# MiniDC.net
KiCad netlist of a schematic drawn in EAGLE
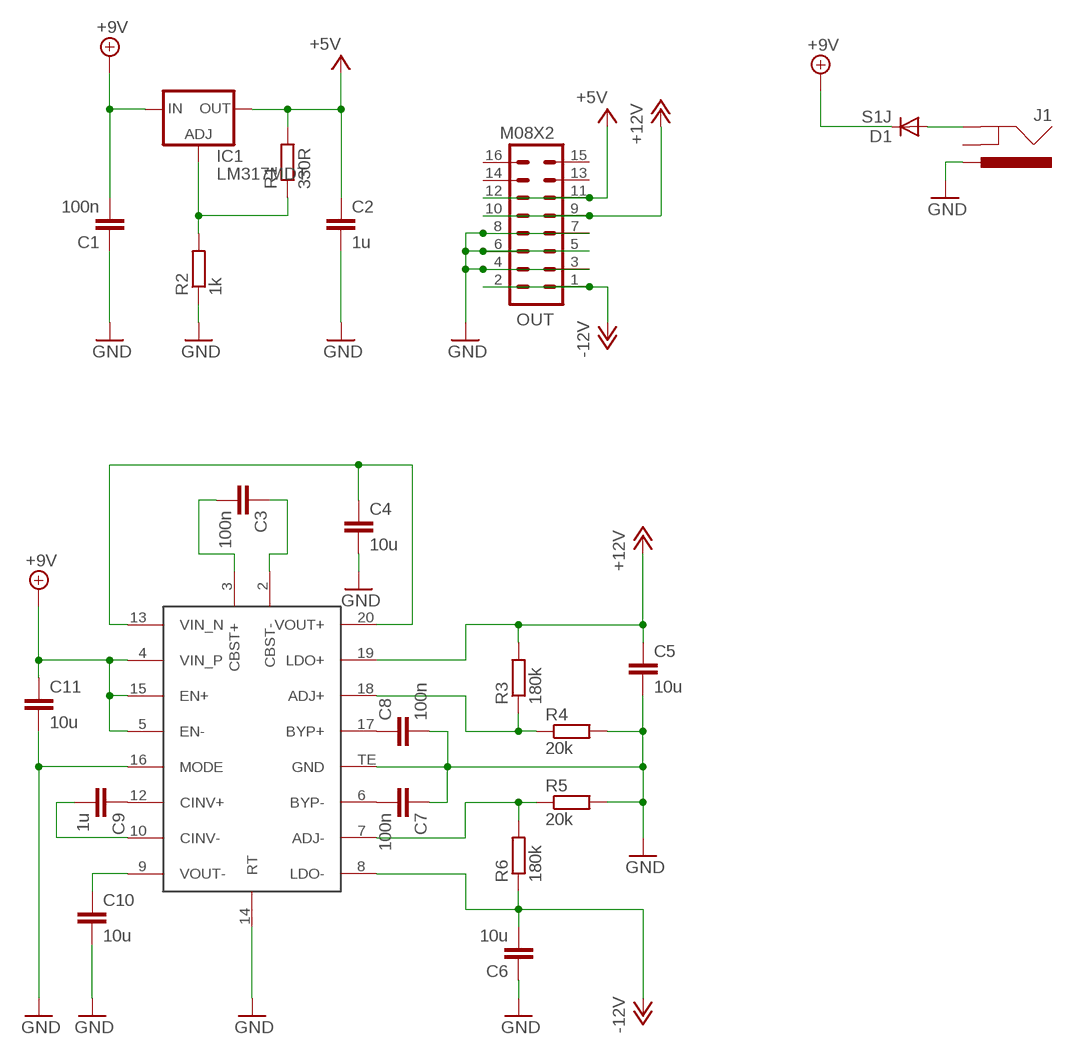
[diagram p0: schematic, sheet 1]

(export (version "E")
  (design (tool "Eeschema 10.0.6"))
  (components
    (comp (ref "C1")
      (value "100n")
      (footprint "eagle-import:C0603")
      (libsource (lib "eagle-import") (part "rcl_C-EUC0603"))
    )
    (comp (ref "C2")
      (value "1u")
      (footprint "eagle-import:C1206K")
      (libsource (lib "eagle-import") (part "C-EUC1206K"))
    )
    (comp (ref "C3")
      (value "100n")
      (footprint "eagle-import:C0603")
      (libsource (lib "eagle-import") (part "rcl_C-EUC0603"))
    )
    (comp (ref "C4")
      (value "10u")
      (footprint "eagle-import:C1206K")
      (libsource (lib "eagle-import") (part "C-EUC1206K"))
    )
    (comp (ref "C5")
      (value "10u")
      (footprint "eagle-import:C1206K")
      (libsource (lib "eagle-import") (part "C-EUC1206K"))
    )
    (comp (ref "C6")
      (value "10u")
      (footprint "eagle-import:C1206K")
      (libsource (lib "eagle-import") (part "C-EUC1206K"))
    )
    (comp (ref "C7")
      (value "100n")
      (footprint "eagle-import:C0603")
      (libsource (lib "eagle-import") (part "rcl_C-EUC0603"))
    )
    (comp (ref "C8")
      (value "100n")
      (footprint "eagle-import:C0603")
      (libsource (lib "eagle-import") (part "rcl_C-EUC0603"))
    )
    (comp (ref "C9")
      (value "1u")
      (footprint "eagle-import:C1206")
      (libsource (lib "eagle-import") (part "C-EUC1206"))
    )
    (comp (ref "C10")
      (value "10u")
      (footprint "eagle-import:C1206K")
      (libsource (lib "eagle-import") (part "C-EUC1206K"))
    )
    (comp (ref "C11")
      (value "10u")
      (footprint "eagle-import:C1206K")
      (libsource (lib "eagle-import") (part "C-EUC1206K"))
    )
    (comp (ref "D1")
      (value "S1J")
      (footprint "eagle-import:SMA-DIODE")
      (libsource (lib "eagle-import") (part "DIODESMA"))
    )
    (comp (ref "IC1")
      (value "LM317MDT")
      (footprint "eagle-import:DPACK")
      (libsource (lib "eagle-import") (part "LM317?MDT"))
    )
    (comp (ref "IC2")
      (value "LTC3265")
      (footprint "eagle-import:TSSOP20-TE")
      (libsource (lib "eagle-import") (part "LTC3265"))
    )
    (comp (ref "J1")
      (value "POWER_JACKPTH")
      (footprint "eagle-import:POWER_JACK_PTH")
      (libsource (lib "eagle-import") (part "POWER_JACKPTH"))
    )
    (comp (ref "OUT")
      (value "M08X2")
      (footprint "eagle-import:2X8")
      (libsource (lib "eagle-import") (part "M08X2"))
    )
    (comp (ref "R1")
      (value "330R")
      (footprint "eagle-import:0603")
      (libsource (lib "eagle-import") (part "R-EU_0603"))
    )
    (comp (ref "R2")
      (value "1k")
      (footprint "eagle-import:0603")
      (libsource (lib "eagle-import") (part "R-EU_0603"))
    )
    (comp (ref "R3")
      (value "180k")
      (footprint "eagle-import:0603")
      (libsource (lib "eagle-import") (part "R-EU_0603"))
    )
    (comp (ref "R4")
      (value "20k")
      (footprint "eagle-import:0603")
      (libsource (lib "eagle-import") (part "R-EU_0603"))
    )
    (comp (ref "R5")
      (value "20k")
      (footprint "eagle-import:0603")
      (libsource (lib "eagle-import") (part "R-EU_0603"))
    )
    (comp (ref "R6")
      (value "180k")
      (footprint "eagle-import:0603")
      (libsource (lib "eagle-import") (part "R-EU_0603"))
    )
  )
  (nets
    (net (code "1") (name "+5V") (class "Default")
      (node (ref "C2") (pin "1") (pinfunction "1_1") (pintype "passive"))
      (node (ref "IC1") (pin "4") (pinfunction "OUT_4") (pintype "passive"))
      (node (ref "OUT") (pin "11") (pinfunction "11_11") (pintype "passive"))
      (node (ref "OUT") (pin "12") (pinfunction "12_12") (pintype "passive"))
      (node (ref "R1") (pin "2") (pinfunction "2_2") (pintype "passive"))
    )
    (net (code "2") (name "+9V") (class "Default")
      (node (ref "C1") (pin "2") (pinfunction "2_2") (pintype "passive"))
      (node (ref "C11") (pin "1") (pinfunction "1_1") (pintype "passive"))
      (node (ref "D1") (pin "C") (pinfunction "C_C") (pintype "passive"))
      (node (ref "IC1") (pin "3") (pinfunction "IN_3") (pintype "input"))
      (node (ref "IC2") (pin "15") (pinfunction "EN+_15") (pintype "bidirectional"))
      (node (ref "IC2") (pin "4") (pinfunction "VIN_P_4") (pintype "bidirectional"))
      (node (ref "IC2") (pin "5") (pinfunction "EN-_5") (pintype "bidirectional"))
    )
    (net (code "3") (name "+12V") (class "Default")
      (node (ref "C5") (pin "1") (pinfunction "1_1") (pintype "passive"))
      (node (ref "IC2") (pin "19") (pinfunction "LDO+_19") (pintype "bidirectional"))
      (node (ref "OUT") (pin "10") (pinfunction "10_10") (pintype "passive"))
      (node (ref "OUT") (pin "9") (pinfunction "9_9") (pintype "passive"))
      (node (ref "R3") (pin "2") (pinfunction "2_2") (pintype "passive"))
    )
    (net (code "4") (name "-12V") (class "Default")
      (node (ref "C6") (pin "2") (pinfunction "2_2") (pintype "passive"))
      (node (ref "IC2") (pin "8") (pinfunction "LDO-_8") (pintype "bidirectional"))
      (node (ref "OUT") (pin "1") (pinfunction "1_1") (pintype "passive"))
      (node (ref "OUT") (pin "2") (pinfunction "2_2") (pintype "passive"))
      (node (ref "R6") (pin "1") (pinfunction "1_1") (pintype "passive"))
    )
    (net (code "5") (name "GND") (class "Default")
      (node (ref "C1") (pin "1") (pinfunction "1_1") (pintype "passive"))
      (node (ref "C10") (pin "2") (pinfunction "2_2") (pintype "passive"))
      (node (ref "C11") (pin "2") (pinfunction "2_2") (pintype "passive"))
      (node (ref "C2") (pin "2") (pinfunction "2_2") (pintype "passive"))
      (node (ref "C4") (pin "2") (pinfunction "2_2") (pintype "passive"))
      (node (ref "C5") (pin "2") (pinfunction "2_2") (pintype "passive"))
      (node (ref "C6") (pin "1") (pinfunction "1_1") (pintype "passive"))
      (node (ref "C7") (pin "1") (pinfunction "1_1") (pintype "passive"))
      (node (ref "C8") (pin "2") (pinfunction "2_2") (pintype "passive"))
      (node (ref "IC2") (pin "14") (pinfunction "RT_14") (pintype "bidirectional"))
      (node (ref "IC2") (pin "16") (pinfunction "MODE_16") (pintype "bidirectional"))
      (node (ref "IC2") (pin "TE") (pinfunction "GND_TE") (pintype "bidirectional"))
      (node (ref "J1") (pin "PWR") (pinfunction "PWR_PWR") (pintype "bidirectional"))
      (node (ref "OUT") (pin "3") (pinfunction "3_3") (pintype "passive"))
      (node (ref "OUT") (pin "4") (pinfunction "4_4") (pintype "passive"))
      (node (ref "OUT") (pin "5") (pinfunction "5_5") (pintype "passive"))
      (node (ref "OUT") (pin "6") (pinfunction "6_6") (pintype "passive"))
      (node (ref "OUT") (pin "7") (pinfunction "7_7") (pintype "passive"))
      (node (ref "OUT") (pin "8") (pinfunction "8_8") (pintype "passive"))
      (node (ref "R2") (pin "1") (pinfunction "1_1") (pintype "passive"))
      (node (ref "R4") (pin "2") (pinfunction "2_2") (pintype "passive"))
      (node (ref "R5") (pin "2") (pinfunction "2_2") (pintype "passive"))
    )
    (net (code "6") (name "Net-(D1-PadA)") (class "Default")
      (node (ref "D1") (pin "A") (pinfunction "A_A") (pintype "passive"))
      (node (ref "J1") (pin "GND") (pinfunction "GND_GND") (pintype "bidirectional"))
    )
    (net (code "7") (name "Net-(IC1-ADJ)") (class "Default")
      (node (ref "IC1") (pin "1") (pinfunction "ADJ_1") (pintype "input"))
      (node (ref "R1") (pin "1") (pinfunction "1_1") (pintype "passive"))
      (node (ref "R2") (pin "2") (pinfunction "2_2") (pintype "passive"))
    )
    (net (code "8") (name "Net-(IC2-ADJ+)") (class "Default")
      (node (ref "IC2") (pin "18") (pinfunction "ADJ+_18") (pintype "bidirectional"))
      (node (ref "R3") (pin "1") (pinfunction "1_1") (pintype "passive"))
      (node (ref "R4") (pin "1") (pinfunction "1_1") (pintype "passive"))
    )
    (net (code "9") (name "Net-(IC2-ADJ-)") (class "Default")
      (node (ref "IC2") (pin "7") (pinfunction "ADJ-_7") (pintype "bidirectional"))
      (node (ref "R5") (pin "1") (pinfunction "1_1") (pintype "passive"))
      (node (ref "R6") (pin "2") (pinfunction "2_2") (pintype "passive"))
    )
    (net (code "10") (name "Net-(IC2-BYP+)") (class "Default")
      (node (ref "C8") (pin "1") (pinfunction "1_1") (pintype "passive"))
      (node (ref "IC2") (pin "17") (pinfunction "BYP+_17") (pintype "bidirectional"))
    )
    (net (code "11") (name "Net-(IC2-BYP-)") (class "Default")
      (node (ref "C7") (pin "2") (pinfunction "2_2") (pintype "passive"))
      (node (ref "IC2") (pin "6") (pinfunction "BYP-_6") (pintype "bidirectional"))
    )
    (net (code "12") (name "Net-(IC2-CBST+)") (class "Default")
      (node (ref "C3") (pin "2") (pinfunction "2_2") (pintype "passive"))
      (node (ref "IC2") (pin "3") (pinfunction "CBST+_3") (pintype "bidirectional"))
    )
    (net (code "13") (name "Net-(IC2-CBST-)") (class "Default")
      (node (ref "C3") (pin "1") (pinfunction "1_1") (pintype "passive"))
      (node (ref "IC2") (pin "2") (pinfunction "CBST-_2") (pintype "bidirectional"))
    )
    (net (code "14") (name "Net-(IC2-CINV+)") (class "Default")
      (node (ref "C9") (pin "1") (pinfunction "1_1") (pintype "passive"))
      (node (ref "IC2") (pin "12") (pinfunction "CINV+_12") (pintype "bidirectional"))
    )
    (net (code "15") (name "Net-(IC2-CINV-)") (class "Default")
      (node (ref "C9") (pin "2") (pinfunction "2_2") (pintype "passive"))
      (node (ref "IC2") (pin "10") (pinfunction "CINV-_10") (pintype "bidirectional"))
    )
    (net (code "16") (name "Net-(IC2-VIN_N)") (class "Default")
      (node (ref "C4") (pin "1") (pinfunction "1_1") (pintype "passive"))
      (node (ref "IC2") (pin "13") (pinfunction "VIN_N_13") (pintype "bidirectional"))
      (node (ref "IC2") (pin "20") (pinfunction "VOUT+_20") (pintype "bidirectional"))
    )
    (net (code "17") (name "Net-(IC2-VOUT-)") (class "Default")
      (node (ref "C10") (pin "1") (pinfunction "1_1") (pintype "passive"))
      (node (ref "IC2") (pin "9") (pinfunction "VOUT-_9") (pintype "bidirectional"))
    )
    (net (code "18") (name "unconnected-(J1-PadGNDBREAK)") (class "Default")
      (node (ref "J1") (pin "GNDBREAK") (pinfunction "GNDBREAK_GNDBREAK") (pintype "bidirectional"))
    )
    (net (code "19") (name "unconnected-(OUT-Pad13)") (class "Default")
      (node (ref "OUT") (pin "13") (pinfunction "13_13") (pintype "passive"))
    )
    (net (code "20") (name "unconnected-(OUT-Pad14)") (class "Default")
      (node (ref "OUT") (pin "14") (pinfunction "14_14") (pintype "passive"))
    )
    (net (code "21") (name "unconnected-(OUT-Pad15)") (class "Default")
      (node (ref "OUT") (pin "15") (pinfunction "15_15") (pintype "passive"))
    )
    (net (code "22") (name "unconnected-(OUT-Pad16)") (class "Default")
      (node (ref "OUT") (pin "16") (pinfunction "16_16") (pintype "passive"))
    )
  )
)
